# design.net
KiCad netlist of a schematic drawn in Altium Designer
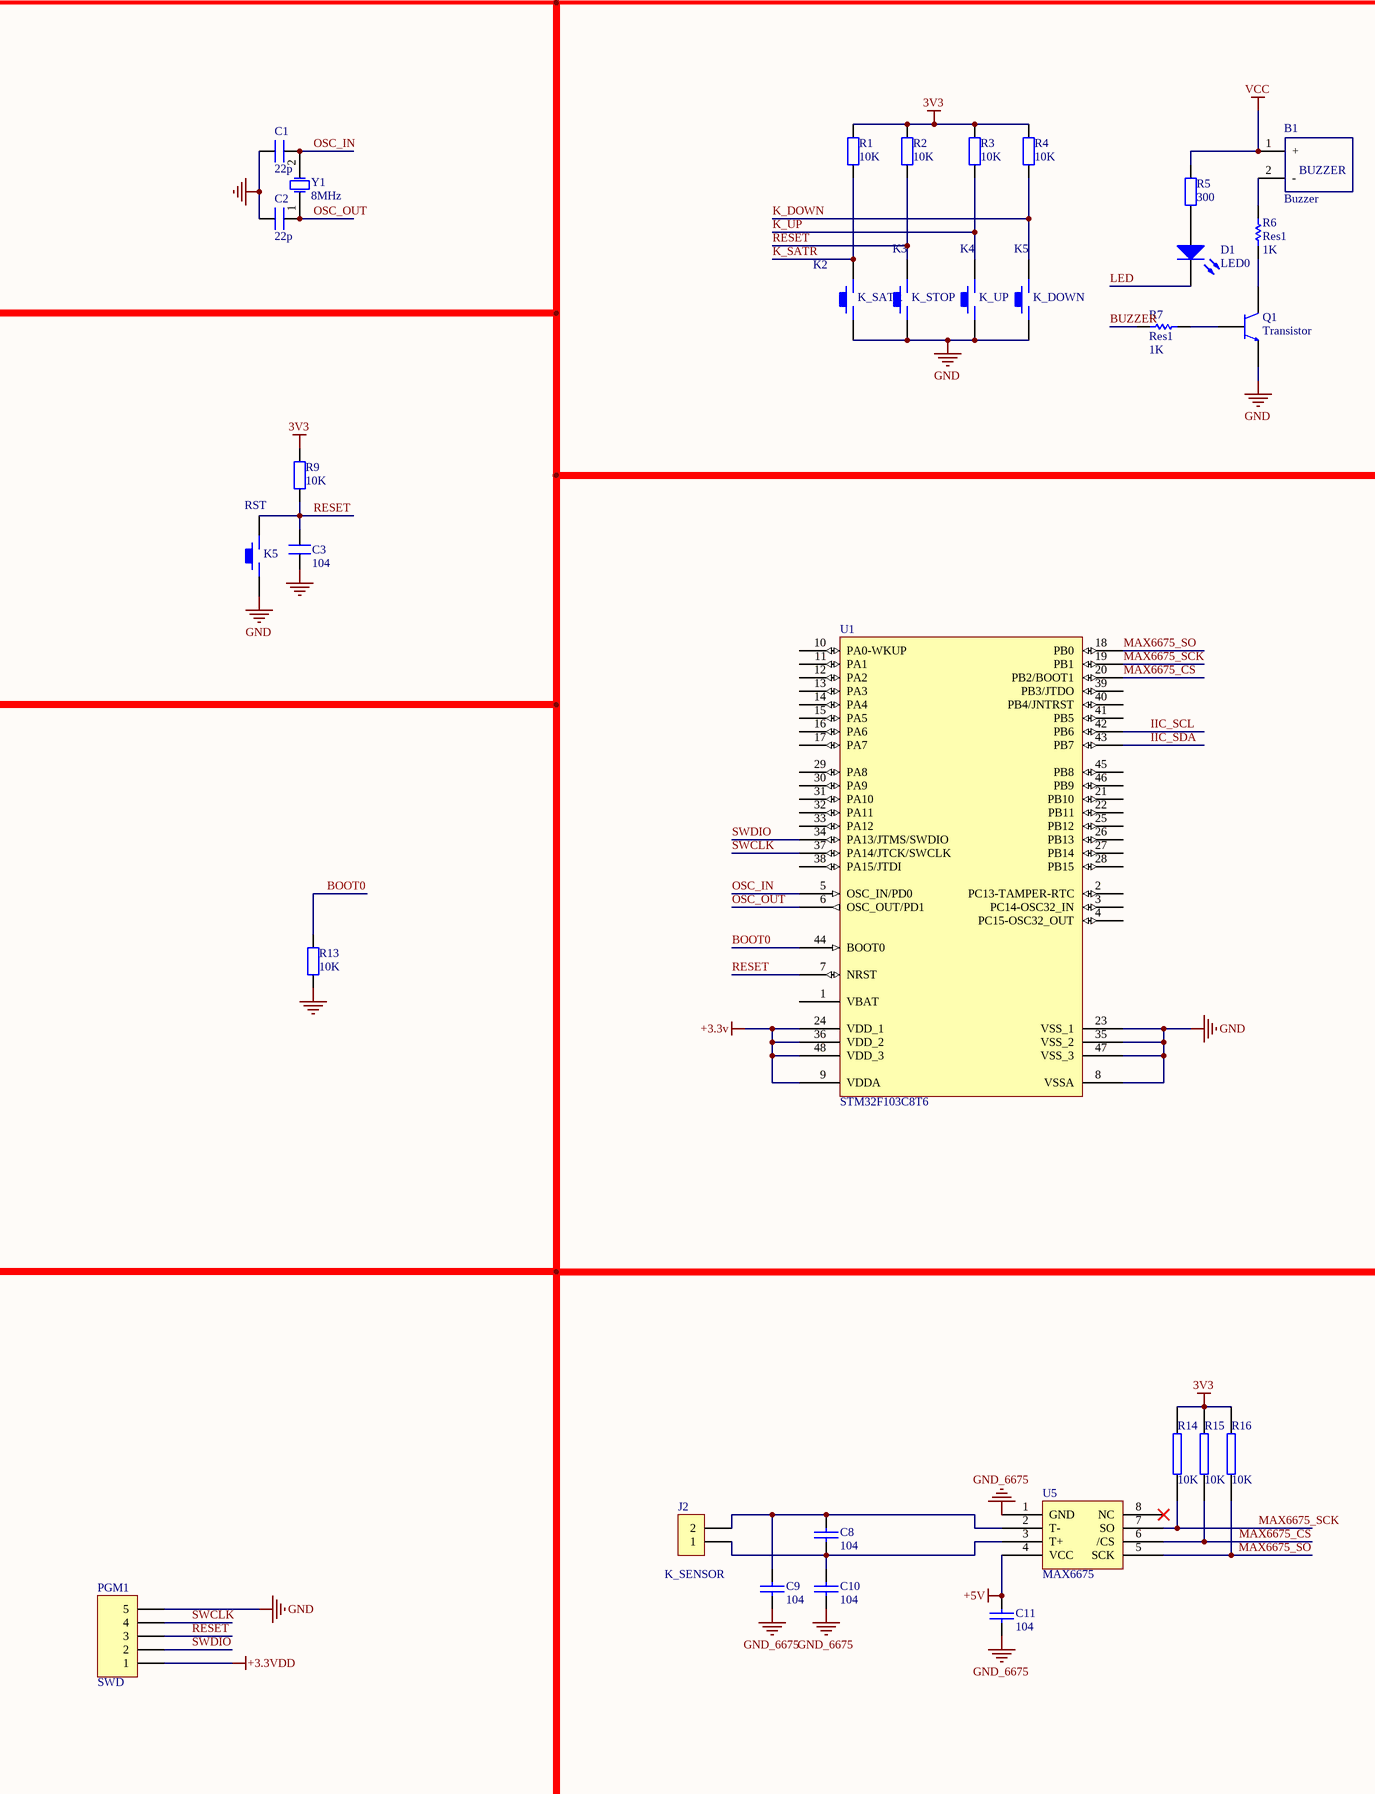
[diagram p0: 原理图.SchDoc, left]
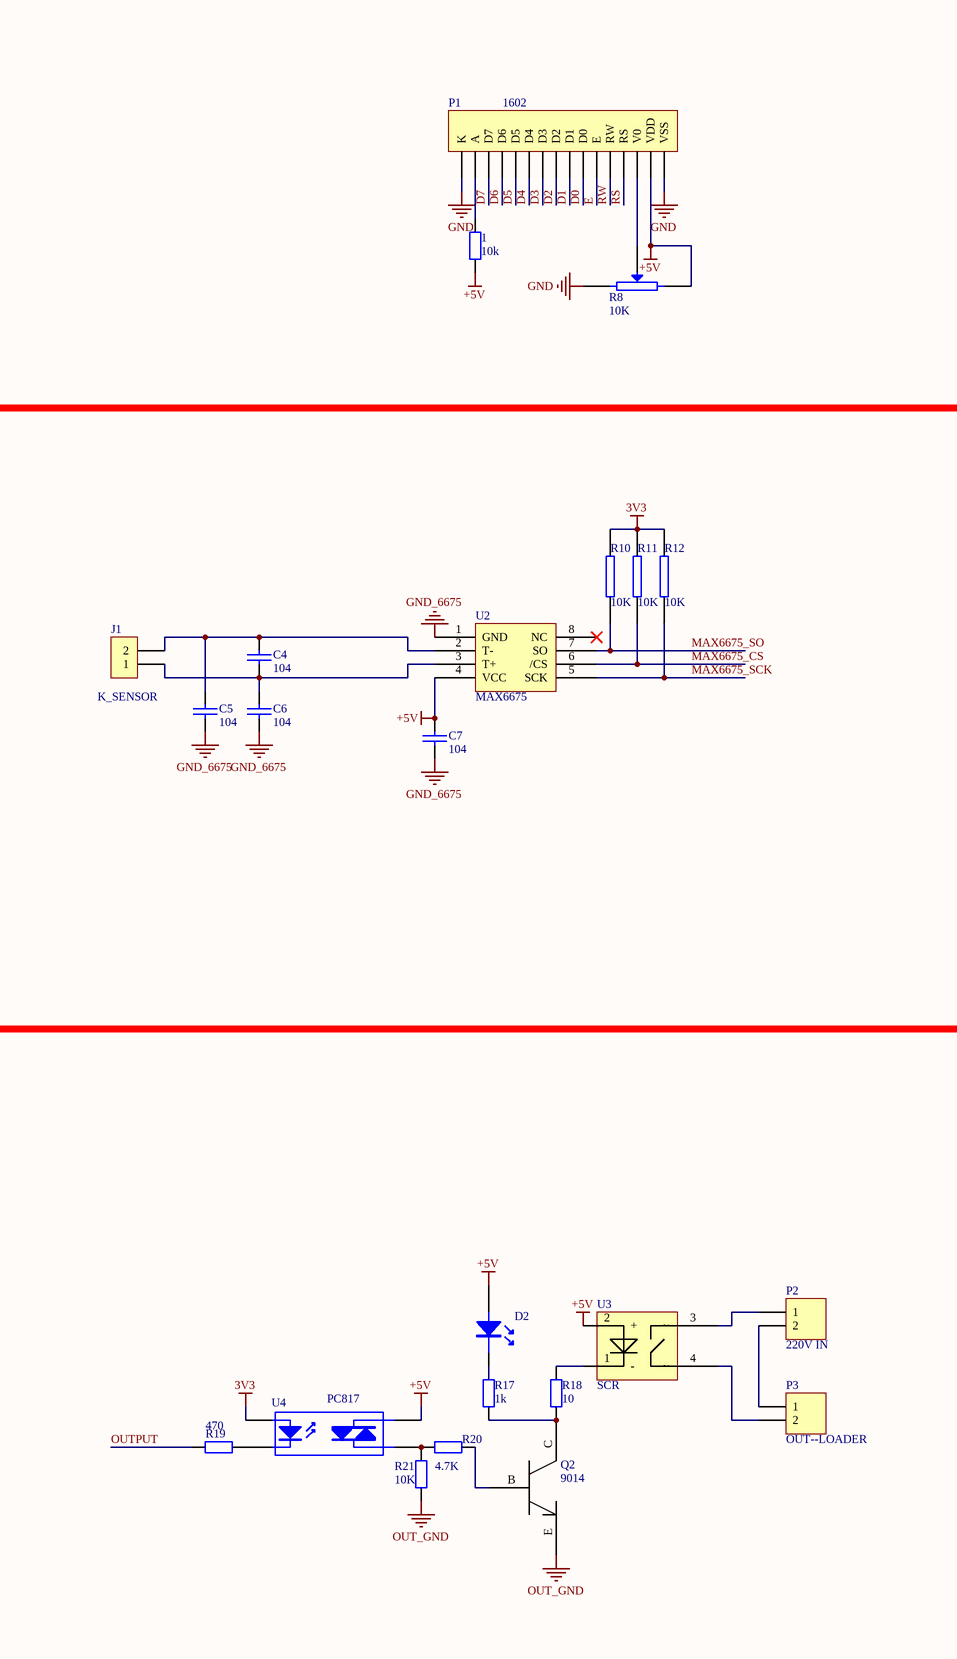
[diagram p1: 原理图.SchDoc, right]

(export (version "E")
  (design (tool "Eeschema 10.0.6"))
  (components
    (comp (ref "1")
      (value "10k")
      (footprint "AXIAL-0.4")
      (description "Resistor")
      (fields (field (name "PUBLISHER") "Altium Limited"))
      (libsource (lib "") (part "Res2_2"))
    )
    (comp (ref "B1") (value "Buzzer") (footprint "BUZZER") (libsource (lib "Second Version") (part "Buzzer")))
    (comp (ref "C1") (value "22p") (footprint "1206") (libsource (lib "MiniSTM32 V3.0封装库") (part "C")))
    (comp (ref "C2") (value "22p") (footprint "1206") (libsource (lib "MiniSTM32 V3.0封装库") (part "C")))
    (comp (ref "C3") (value "104") (footprint "1206") (libsource (lib "MiniSTM32 V3.0封装库") (part "C")))
    (comp (ref "C4")
      (value "104")
      (footprint "1206")
      (description "Capacitor")
      (libsource (lib "电容") (part "普通电容"))
    )
    (comp (ref "C5")
      (value "104")
      (footprint "1206")
      (description "Capacitor")
      (libsource (lib "电容") (part "普通电容"))
    )
    (comp (ref "C6")
      (value "104")
      (footprint "1206")
      (description "Capacitor")
      (libsource (lib "电容") (part "普通电容"))
    )
    (comp (ref "C7")
      (value "104")
      (footprint "1206")
      (description "Capacitor")
      (libsource (lib "电容") (part "普通电容"))
    )
    (comp (ref "C8")
      (value "104")
      (footprint "1206")
      (description "Capacitor")
      (libsource (lib "电容") (part "普通电容"))
    )
    (comp (ref "C9")
      (value "104")
      (footprint "1206")
      (description "Capacitor")
      (libsource (lib "电容") (part "普通电容"))
    )
    (comp (ref "C10")
      (value "104")
      (footprint "1206")
      (description "Capacitor")
      (libsource (lib "电容") (part "普通电容"))
    )
    (comp (ref "C11")
      (value "104")
      (footprint "1206")
      (description "Capacitor")
      (libsource (lib "电容") (part "普通电容"))
    )
    (comp (ref "D1")
      (value "LED0")
      (footprint "LED-0")
      (description "Typical INFRARED GaAs LED")
      (fields (field (name "PUBLISHER") "Altium Limited"))
      (libsource (lib "Miscellaneous Devices") (part "LED0"))
    )
    (comp (ref "D2") (value "~") (footprint "李建国1:LED") (libsource (lib "二极管") (part "发光二极管")))
    (comp (ref "J1")
      (value "K_SENSOR")
      (footprint "OUT_CJ")
      (description "Connector")
      (libsource (lib "Miscellaneous Devices") (part "CON2"))
    )
    (comp (ref "J2")
      (value "K_SENSOR")
      (footprint "OUT_CJ")
      (description "Connector")
      (libsource (lib "Miscellaneous Devices") (part "CON2"))
    )
    (comp (ref "K5") (value "RST") (footprint "KEY_M") (libsource (lib "底板封装库") (part "KEY_M")))
    (comp (ref "K_DOWN") (value "K5") (footprint "KEY_M") (libsource (lib "底板封装库") (part "KEY_M")))
    (comp (ref "K_SATR") (value "K2") (footprint "KEY_M") (libsource (lib "底板封装库") (part "KEY_M")))
    (comp (ref "K_STOP") (value "K3") (footprint "KEY_M") (libsource (lib "底板封装库") (part "KEY_M")))
    (comp (ref "K_UP") (value "K4") (footprint "KEY_M") (libsource (lib "底板封装库") (part "KEY_M")))
    (comp (ref "P1")
      (value "1602")
      (footprint "HDR1X16")
      (description "Header, 16-Pin")
      (fields (field (name "PUBLISHER") "Altium Limited"))
      (libsource (lib "Miscellaneous Connectors") (part "Header 16"))
    )
    (comp (ref "P2")
      (value "220V IN")
      (footprint "OUT_CJ")
      (description "Header, 2-Pin")
      (fields (field (name "PUBLISHER") "Altium Limited"))
      (libsource (lib "Miscellaneous Connectors") (part "Header 2"))
    )
    (comp (ref "P3")
      (value "OUT--LOADER")
      (footprint "OUT_CJ")
      (description "Header, 2-Pin")
      (fields (field (name "PUBLISHER") "Altium Limited"))
      (libsource (lib "Miscellaneous Connectors") (part "Header 2"))
    )
    (comp (ref "PGM1")
      (value "SWD")
      (footprint "HX2.54-5p")
      (description "Header, 5-Pin")
      (fields (field (name "PUBLISHER") "Altium Limited"))
      (libsource (lib "Miscellaneous Connectors") (part "Header 5"))
    )
    (comp (ref "Q1")
      (value "Transistor")
      (footprint "SOT23_TR")
      (libsource (lib "First Version") (part "NPN_Transistor_SOT23"))
    )
    (comp (ref "Q2") (value "9014") (footprint "9014") (libsource (lib "陈志伟2") (part "9014")))
    (comp (ref "R1")
      (value "10K")
      (footprint "1206")
      (description "Resistor")
      (fields (field (name "PUBLISHER") "Altium Limited"))
      (libsource (lib "") (part "Res2_1"))
    )
    (comp (ref "R2")
      (value "10K")
      (footprint "1206")
      (description "Resistor")
      (fields (field (name "PUBLISHER") "Altium Limited"))
      (libsource (lib "") (part "Res2_1"))
    )
    (comp (ref "R3")
      (value "10K")
      (footprint "1206")
      (description "Resistor")
      (fields (field (name "PUBLISHER") "Altium Limited"))
      (libsource (lib "") (part "Res2_1"))
    )
    (comp (ref "R4")
      (value "10K")
      (footprint "1206")
      (description "Resistor")
      (fields (field (name "PUBLISHER") "Altium Limited"))
      (libsource (lib "") (part "Res2_1"))
    )
    (comp (ref "R5")
      (value "300")
      (footprint "AXIAL-0.4")
      (description "Resistor")
      (fields (field (name "PUBLISHER") "Altium Limited"))
      (libsource (lib "") (part "Res2_2"))
    )
    (comp (ref "R6")
      (value "Res1")
      (footprint "SMD0805_RES")
      (description "Resistor")
      (fields (field (name "ALTIUM_VALUE") "1K") (field (name "PUBLISHER") "Altium Limited"))
      (libsource (lib "Miscellaneous Devices") (part "Res1"))
    )
    (comp (ref "R7")
      (value "Res1")
      (footprint "SMD0805_RES")
      (description "Resistor")
      (fields (field (name "ALTIUM_VALUE") "1K") (field (name "PUBLISHER") "Altium Limited"))
      (libsource (lib "Miscellaneous Devices") (part "Res1"))
    )
    (comp (ref "R8")
      (value "10K")
      (footprint "VR")
      (description "Potentiometer")
      (libsource (lib "电阻") (part "RESVR"))
    )
    (comp (ref "R9")
      (value "10K")
      (footprint "1206")
      (description "Resistor")
      (fields (field (name "PUBLISHER") "Altium Limited"))
      (libsource (lib "Miscellaneous Devices") (part "Res2"))
    )
    (comp (ref "R10") (value "10K") (footprint "1206") (libsource (lib "*") (part "RES2")))
    (comp (ref "R11") (value "10K") (footprint "1206") (libsource (lib "*") (part "RES2")))
    (comp (ref "R12") (value "10K") (footprint "1206") (libsource (lib "*") (part "RES2")))
    (comp (ref "R13")
      (value "10K")
      (footprint "1206")
      (description "Resistor")
      (fields (field (name "PUBLISHER") "Altium Limited"))
      (libsource (lib "Miscellaneous Devices") (part "Res2"))
    )
    (comp (ref "R14") (value "10K") (footprint "1206") (libsource (lib "*") (part "RES2")))
    (comp (ref "R15") (value "10K") (footprint "1206") (libsource (lib "*") (part "RES2")))
    (comp (ref "R16") (value "10K") (footprint "1206") (libsource (lib "*") (part "RES2")))
    (comp (ref "R17")
      (value "1k")
      (footprint "1206")
      (description "Resistor")
      (fields (field (name "PUBLISHER") "Altium Limited"))
      (libsource (lib "") (part "Res2_1"))
    )
    (comp (ref "R18")
      (value "10")
      (footprint "1206")
      (description "Resistor")
      (fields (field (name "PUBLISHER") "Altium Limited"))
      (libsource (lib "") (part "Res2_1"))
    )
    (comp (ref "R19")
      (value "470")
      (footprint "1206")
      (description "Resistor")
      (fields (field (name "PUBLISHER") "Altium Limited"))
      (libsource (lib "Miscellaneous Devices") (part "Res2"))
    )
    (comp (ref "R20")
      (value "4.7K")
      (footprint "1206")
      (description "Resistor")
      (fields (field (name "PUBLISHER") "Altium Limited"))
      (libsource (lib "Miscellaneous Devices") (part "Res2"))
    )
    (comp (ref "R21")
      (value "10K")
      (footprint "1206")
      (description "Resistor")
      (fields (field (name "PUBLISHER") "Altium Limited"))
      (libsource (lib "") (part "Res2_1"))
    )
    (comp (ref "U1")
      (value "STM32F103C8T6")
      (footprint "LQFP48_N")
      (description "STM32 ARM-based 32-bit MCU with 64 Kbytes Flash, 48-pin LQFP, Industrial Temperature")
      (fields (field (name "PUBLISHER") "Altium Limited"))
      (libsource (lib "ST Microcontroller 32-Bit STM32") (part "STM32F103C8T6"))
    )
    (comp (ref "U2") (value "MAX6675") (footprint "SO-8") (libsource (lib "温控库") (part "MAX6675")))
    (comp (ref "U3") (value "SCR") (footprint "SCR") (libsource (lib "*") (part "SCR")))
    (comp (ref "U4")
      (value "PC817")
      (footprint "pc817")
      (libsource (lib "Miscellaneous Devices") (part "OPTOTRIAC"))
    )
    (comp (ref "U5") (value "MAX6675") (footprint "SO-8") (libsource (lib "温控库") (part "MAX6675")))
    (comp (ref "Y1")
      (value "8MHz")
      (footprint "XTAL_US")
      (description "Crystal Oscillator")
      (fields (field (name "PUBLISHER") "Altium Limited"))
      (libsource (lib "MiniSTM32 V3.0封装库") (part "XTAL"))
    )
  )
  (nets
    (net (code "1") (name "+3.3VDD") (class "Default")
      (node (ref "PGM1") (pin "1") (pinfunction "1_1") (pintype "passive"))
    )
    (net (code "2") (name "+3.3v") (class "Default")
      (node (ref "U1") (pin "24") (pinfunction "VDD_1_24") (pintype "power_in"))
      (node (ref "U1") (pin "36") (pinfunction "VDD_2_36") (pintype "power_in"))
      (node (ref "U1") (pin "48") (pinfunction "VDD_3_48") (pintype "power_in"))
      (node (ref "U1") (pin "9") (pinfunction "VDDA_9") (pintype "power_in"))
    )
    (net (code "3") (name "+5V") (class "Default")
      (node (ref "1") (pin "1") (pinfunction "1_1") (pintype "passive"))
      (node (ref "C11") (pin "1") (pinfunction "1_1") (pintype "passive"))
      (node (ref "C7") (pin "1") (pinfunction "1_1") (pintype "passive"))
      (node (ref "D2") (pin "A") (pinfunction "1_A") (pintype "passive"))
      (node (ref "P1") (pin "2") (pinfunction "VDD_2") (pintype "passive"))
      (node (ref "R8") (pin "2") (pinfunction "2_2") (pintype "passive"))
      (node (ref "U2") (pin "4") (pinfunction "VCC_4") (pintype "passive"))
      (node (ref "U3") (pin "2") (pinfunction "+_2") (pintype "passive"))
      (node (ref "U4") (pin "3") (pinfunction "A/K_3") (pintype "passive"))
      (node (ref "U5") (pin "4") (pinfunction "VCC_4") (pintype "passive"))
    )
    (net (code "4") (name "/BOOT0") (class "Default")
      (node (ref "R13") (pin "1") (pinfunction "1_1") (pintype "passive"))
      (node (ref "U1") (pin "44") (pinfunction "BOOT0_44") (pintype "input"))
    )
    (net (code "5") (name "/BUZZER") (class "Default")
      (node (ref "R7") (pin "1") (pinfunction "1_1") (pintype "passive"))
    )
    (net (code "6") (name "/D0") (class "Default")
      (node (ref "P1") (pin "7") (pinfunction "D0_7") (pintype "passive"))
    )
    (net (code "7") (name "/D1") (class "Default")
      (node (ref "P1") (pin "8") (pinfunction "D1_8") (pintype "passive"))
    )
    (net (code "8") (name "/D2") (class "Default")
      (node (ref "P1") (pin "9") (pinfunction "D2_9") (pintype "passive"))
    )
    (net (code "9") (name "/D3") (class "Default")
      (node (ref "P1") (pin "10") (pinfunction "D3_10") (pintype "passive"))
    )
    (net (code "10") (name "/D4") (class "Default")
      (node (ref "P1") (pin "11") (pinfunction "D4_11") (pintype "passive"))
    )
    (net (code "11") (name "/D5") (class "Default")
      (node (ref "P1") (pin "12") (pinfunction "D5_12") (pintype "passive"))
    )
    (net (code "12") (name "/D6") (class "Default")
      (node (ref "P1") (pin "13") (pinfunction "D6_13") (pintype "passive"))
    )
    (net (code "13") (name "/D7") (class "Default")
      (node (ref "P1") (pin "14") (pinfunction "D7_14") (pintype "passive"))
    )
    (net (code "14") (name "/E") (class "Default")
      (node (ref "P1") (pin "6") (pinfunction "E_6") (pintype "passive"))
    )
    (net (code "15") (name "/IIC_SCL") (class "Default")
      (node (ref "U1") (pin "42") (pinfunction "PB6_42") (pintype "bidirectional"))
    )
    (net (code "16") (name "/IIC_SDA") (class "Default")
      (node (ref "U1") (pin "43") (pinfunction "PB7_43") (pintype "bidirectional"))
    )
    (net (code "17") (name "/K_DOWN") (class "Default")
      (node (ref "K_DOWN") (pin "2") (pinfunction "2_2") (pintype "passive"))
      (node (ref "R4") (pin "1") (pinfunction "1_1") (pintype "passive"))
    )
    (net (code "18") (name "/K_SATR") (class "Default")
      (node (ref "K_SATR") (pin "2") (pinfunction "2_2") (pintype "passive"))
      (node (ref "R1") (pin "1") (pinfunction "1_1") (pintype "passive"))
    )
    (net (code "19") (name "/K_UP") (class "Default")
      (node (ref "K_UP") (pin "2") (pinfunction "2_2") (pintype "passive"))
      (node (ref "R3") (pin "1") (pinfunction "1_1") (pintype "passive"))
    )
    (net (code "20") (name "/LED") (class "Default")
      (node (ref "D1") (pin "2") (pinfunction "K_2") (pintype "passive"))
    )
    (net (code "21") (name "/MAX6675_CS") (class "Default")
      (node (ref "R11") (pin "1") (pinfunction "1_1") (pintype "passive"))
      (node (ref "R15") (pin "1") (pinfunction "1_1") (pintype "passive"))
      (node (ref "U1") (pin "20") (pinfunction "PB2/BOOT1_20") (pintype "bidirectional"))
      (node (ref "U2") (pin "6") (pinfunction "/CS_6") (pintype "passive"))
      (node (ref "U5") (pin "6") (pinfunction "/CS_6") (pintype "passive"))
    )
    (net (code "22") (name "/MAX6675_SCK") (class "Default")
      (node (ref "R12") (pin "1") (pinfunction "1_1") (pintype "passive"))
      (node (ref "R14") (pin "1") (pinfunction "1_1") (pintype "passive"))
      (node (ref "U1") (pin "19") (pinfunction "PB1_19") (pintype "bidirectional"))
      (node (ref "U2") (pin "5") (pinfunction "SCK_5") (pintype "passive"))
      (node (ref "U5") (pin "7") (pinfunction "SO_7") (pintype "passive"))
    )
    (net (code "23") (name "/MAX6675_SO") (class "Default")
      (node (ref "R10") (pin "1") (pinfunction "1_1") (pintype "passive"))
      (node (ref "R16") (pin "1") (pinfunction "1_1") (pintype "passive"))
      (node (ref "U1") (pin "18") (pinfunction "PB0_18") (pintype "bidirectional"))
      (node (ref "U2") (pin "7") (pinfunction "SO_7") (pintype "passive"))
      (node (ref "U5") (pin "5") (pinfunction "SCK_5") (pintype "passive"))
    )
    (net (code "24") (name "/OSC_IN") (class "Default")
      (node (ref "C1") (pin "1") (pintype "passive"))
      (node (ref "U1") (pin "5") (pinfunction "OSC_IN/PD0_5") (pintype "input"))
      (node (ref "Y1") (pin "2") (pinfunction "OSC2_2") (pintype "passive"))
    )
    (net (code "25") (name "/OSC_OUT") (class "Default")
      (node (ref "C2") (pin "2") (pintype "passive"))
      (node (ref "U1") (pin "6") (pinfunction "OSC_OUT/PD1_6") (pintype "output"))
      (node (ref "Y1") (pin "1") (pinfunction "OSC1_1") (pintype "passive"))
    )
    (net (code "26") (name "/OUTPUT") (class "Default")
      (node (ref "R19") (pin "2") (pinfunction "2_2") (pintype "passive"))
    )
    (net (code "27") (name "/RESET") (class "Default")
      (node (ref "C3") (pin "1") (pintype "passive"))
      (node (ref "K5") (pin "2") (pinfunction "2_2") (pintype "passive"))
      (node (ref "K_STOP") (pin "2") (pinfunction "2_2") (pintype "passive"))
      (node (ref "PGM1") (pin "3") (pinfunction "3_3") (pintype "passive"))
      (node (ref "R2") (pin "1") (pinfunction "1_1") (pintype "passive"))
      (node (ref "R9") (pin "2") (pinfunction "2_2") (pintype "passive"))
      (node (ref "U1") (pin "7") (pinfunction "NRST_7") (pintype "bidirectional"))
    )
    (net (code "28") (name "/RS") (class "Default")
      (node (ref "P1") (pin "4") (pinfunction "RS_4") (pintype "passive"))
    )
    (net (code "29") (name "/RW") (class "Default")
      (node (ref "P1") (pin "5") (pinfunction "RW_5") (pintype "passive"))
    )
    (net (code "30") (name "/SWCLK") (class "Default")
      (node (ref "PGM1") (pin "4") (pinfunction "4_4") (pintype "passive"))
      (node (ref "U1") (pin "37") (pinfunction "PA14/JTCK/SWCLK_37") (pintype "bidirectional"))
    )
    (net (code "31") (name "/SWDIO") (class "Default")
      (node (ref "PGM1") (pin "2") (pinfunction "2_2") (pintype "passive"))
      (node (ref "U1") (pin "34") (pinfunction "PA13/JTMS/SWDIO_34") (pintype "bidirectional"))
    )
    (net (code "32") (name "3V3") (class "Default")
      (node (ref "R1") (pin "2") (pinfunction "2_2") (pintype "passive"))
      (node (ref "R10") (pin "2") (pinfunction "2_2") (pintype "passive"))
      (node (ref "R11") (pin "2") (pinfunction "2_2") (pintype "passive"))
      (node (ref "R12") (pin "2") (pinfunction "2_2") (pintype "passive"))
      (node (ref "R14") (pin "2") (pinfunction "2_2") (pintype "passive"))
      (node (ref "R15") (pin "2") (pinfunction "2_2") (pintype "passive"))
      (node (ref "R16") (pin "2") (pinfunction "2_2") (pintype "passive"))
      (node (ref "R2") (pin "2") (pinfunction "2_2") (pintype "passive"))
      (node (ref "R3") (pin "2") (pinfunction "2_2") (pintype "passive"))
      (node (ref "R4") (pin "2") (pinfunction "2_2") (pintype "passive"))
      (node (ref "R9") (pin "1") (pinfunction "1_1") (pintype "passive"))
      (node (ref "U4") (pin "1") (pinfunction "A_1") (pintype "passive"))
    )
    (net (code "33") (name "GND") (class "Default")
      (node (ref "C1") (pin "2") (pintype "passive"))
      (node (ref "C2") (pin "1") (pintype "passive"))
      (node (ref "C3") (pin "2") (pintype "passive"))
      (node (ref "K5") (pin "1") (pinfunction "1_1") (pintype "passive"))
      (node (ref "K_DOWN") (pin "1") (pinfunction "1_1") (pintype "passive"))
      (node (ref "K_SATR") (pin "1") (pinfunction "1_1") (pintype "passive"))
      (node (ref "K_STOP") (pin "1") (pinfunction "1_1") (pintype "passive"))
      (node (ref "K_UP") (pin "1") (pinfunction "1_1") (pintype "passive"))
      (node (ref "P1") (pin "1") (pinfunction "VSS_1") (pintype "passive"))
      (node (ref "P1") (pin "16") (pinfunction "K_16") (pintype "passive"))
      (node (ref "PGM1") (pin "5") (pinfunction "5_5") (pintype "passive"))
      (node (ref "Q1") (pin "2") (pinfunction "2_2") (pintype "passive"))
      (node (ref "R13") (pin "2") (pinfunction "2_2") (pintype "passive"))
      (node (ref "R8") (pin "1") (pinfunction "1_1") (pintype "passive"))
      (node (ref "U1") (pin "23") (pinfunction "VSS_1_23") (pintype "power_in"))
      (node (ref "U1") (pin "35") (pinfunction "VSS_2_35") (pintype "power_in"))
      (node (ref "U1") (pin "47") (pinfunction "VSS_3_47") (pintype "power_in"))
      (node (ref "U1") (pin "8") (pinfunction "VSSA_8") (pintype "power_in"))
    )
    (net (code "34") (name "GND_6675") (class "Default")
      (node (ref "C10") (pin "2") (pinfunction "2_2") (pintype "passive"))
      (node (ref "C11") (pin "2") (pinfunction "2_2") (pintype "passive"))
      (node (ref "C5") (pin "2") (pinfunction "2_2") (pintype "passive"))
      (node (ref "C6") (pin "2") (pinfunction "2_2") (pintype "passive"))
      (node (ref "C7") (pin "2") (pinfunction "2_2") (pintype "passive"))
      (node (ref "C9") (pin "2") (pinfunction "2_2") (pintype "passive"))
      (node (ref "U2") (pin "1") (pinfunction "GND_1") (pintype "passive"))
      (node (ref "U5") (pin "1") (pinfunction "GND_1") (pintype "passive"))
    )
    (net (code "35") (name "Net-(B1--)") (class "Default")
      (node (ref "B1") (pin "2") (pinfunction "-_2") (pintype "passive"))
      (node (ref "R6") (pin "2") (pinfunction "2_2") (pintype "passive"))
    )
    (net (code "36") (name "Net-(D1-A)") (class "Default")
      (node (ref "D1") (pin "1") (pinfunction "A_1") (pintype "passive"))
      (node (ref "R5") (pin "1") (pinfunction "1_1") (pintype "passive"))
    )
    (net (code "37") (name "Net-(D2-2)") (class "Default")
      (node (ref "D2") (pin "K") (pinfunction "2_K") (pintype "passive"))
      (node (ref "R17") (pin "2") (pinfunction "2_2") (pintype "passive"))
    )
    (net (code "38") (name "Net-(P1-A)") (class "Default")
      (node (ref "1") (pin "2") (pinfunction "2_2") (pintype "passive"))
      (node (ref "P1") (pin "15") (pinfunction "A_15") (pintype "passive"))
    )
    (net (code "39") (name "Net-(P1-V0)") (class "Default")
      (node (ref "P1") (pin "3") (pinfunction "V0_3") (pintype "passive"))
      (node (ref "R8") (pin "3") (pinfunction "W_3") (pintype "passive"))
    )
    (net (code "40") (name "Net-(P2-Pad1)") (class "Default")
      (node (ref "P2") (pin "1") (pinfunction "1_1") (pintype "passive"))
      (node (ref "U3") (pin "3") (pinfunction "~_3") (pintype "passive"))
    )
    (net (code "41") (name "Net-(P2-Pad2)") (class "Default")
      (node (ref "P2") (pin "2") (pinfunction "2_2") (pintype "passive"))
      (node (ref "P3") (pin "1") (pinfunction "1_1") (pintype "passive"))
    )
    (net (code "42") (name "Net-(P3-Pad2)") (class "Default")
      (node (ref "P3") (pin "2") (pinfunction "2_2") (pintype "passive"))
      (node (ref "U3") (pin "4") (pinfunction "~_4") (pintype "passive"))
    )
    (net (code "43") (name "Net-(Q1-Pad1)") (class "Default")
      (node (ref "Q1") (pin "1") (pinfunction "1_1") (pintype "passive"))
      (node (ref "R7") (pin "2") (pinfunction "2_2") (pintype "passive"))
    )
    (net (code "44") (name "Net-(Q1-Pad3)") (class "Default")
      (node (ref "Q1") (pin "3") (pinfunction "3_3") (pintype "passive"))
      (node (ref "R6") (pin "1") (pinfunction "1_1") (pintype "passive"))
    )
    (net (code "45") (name "Net-(Q2-PadB)") (class "Default")
      (node (ref "Q2") (pin "B") (pinfunction "B_B") (pintype "passive"))
      (node (ref "R20") (pin "1") (pinfunction "1_1") (pintype "passive"))
    )
    (net (code "46") (name "Net-(Q2-PadC)") (class "Default")
      (node (ref "Q2") (pin "C") (pinfunction "C_C") (pintype "passive"))
      (node (ref "R17") (pin "1") (pinfunction "1_1") (pintype "passive"))
      (node (ref "R18") (pin "1") (pinfunction "1_1") (pintype "passive"))
    )
    (net (code "47") (name "Net-(R20-Pad2)") (class "Default")
      (node (ref "R20") (pin "2") (pinfunction "2_2") (pintype "passive"))
      (node (ref "R21") (pin "2") (pinfunction "2_2") (pintype "passive"))
      (node (ref "U4") (pin "4") (pinfunction "A/K_4") (pintype "passive"))
    )
    (net (code "48") (name "Net-(U2-T+)") (class "Default")
      (node (ref "C4") (pin "2") (pinfunction "2_2") (pintype "passive"))
      (node (ref "C6") (pin "1") (pinfunction "1_1") (pintype "passive"))
      (node (ref "J1") (pin "1") (pinfunction "1_1") (pintype "passive"))
      (node (ref "U2") (pin "3") (pinfunction "T+_3") (pintype "passive"))
    )
    (net (code "49") (name "Net-(U2-T-)") (class "Default")
      (node (ref "C4") (pin "1") (pinfunction "1_1") (pintype "passive"))
      (node (ref "C5") (pin "1") (pinfunction "1_1") (pintype "passive"))
      (node (ref "J1") (pin "2") (pinfunction "2_2") (pintype "passive"))
      (node (ref "U2") (pin "2") (pinfunction "T-_2") (pintype "passive"))
    )
    (net (code "50") (name "Net-(U3--)") (class "Default")
      (node (ref "R18") (pin "2") (pinfunction "2_2") (pintype "passive"))
      (node (ref "U3") (pin "1") (pinfunction "-_1") (pintype "passive"))
    )
    (net (code "51") (name "Net-(U4-K)") (class "Default")
      (node (ref "R19") (pin "1") (pinfunction "1_1") (pintype "passive"))
      (node (ref "U4") (pin "2") (pinfunction "K_2") (pintype "passive"))
    )
    (net (code "52") (name "Net-(U5-T+)") (class "Default")
      (node (ref "C10") (pin "1") (pinfunction "1_1") (pintype "passive"))
      (node (ref "C8") (pin "2") (pinfunction "2_2") (pintype "passive"))
      (node (ref "J2") (pin "1") (pinfunction "1_1") (pintype "passive"))
      (node (ref "U5") (pin "3") (pinfunction "T+_3") (pintype "passive"))
    )
    (net (code "53") (name "Net-(U5-T-)") (class "Default")
      (node (ref "C8") (pin "1") (pinfunction "1_1") (pintype "passive"))
      (node (ref "C9") (pin "1") (pinfunction "1_1") (pintype "passive"))
      (node (ref "J2") (pin "2") (pinfunction "2_2") (pintype "passive"))
      (node (ref "U5") (pin "2") (pinfunction "T-_2") (pintype "passive"))
    )
    (net (code "54") (name "OUT_GND") (class "Default")
      (node (ref "Q2") (pin "E") (pinfunction "E_E") (pintype "passive"))
      (node (ref "R21") (pin "1") (pinfunction "1_1") (pintype "passive"))
    )
    (net (code "55") (name "VCC") (class "Default")
      (node (ref "B1") (pin "1") (pinfunction "+_1") (pintype "passive"))
      (node (ref "R5") (pin "2") (pinfunction "2_2") (pintype "passive"))
    )
    (net (code "56") (name "unconnected-(U1-PA0-WKUP-Pad10)") (class "Default")
      (node (ref "U1") (pin "10") (pinfunction "PA0-WKUP_10") (pintype "bidirectional"))
    )
    (net (code "57") (name "unconnected-(U1-PA1-Pad11)") (class "Default")
      (node (ref "U1") (pin "11") (pinfunction "PA1_11") (pintype "bidirectional"))
    )
    (net (code "58") (name "unconnected-(U1-PA2-Pad12)") (class "Default")
      (node (ref "U1") (pin "12") (pinfunction "PA2_12") (pintype "bidirectional"))
    )
    (net (code "59") (name "unconnected-(U1-PA3-Pad13)") (class "Default")
      (node (ref "U1") (pin "13") (pinfunction "PA3_13") (pintype "bidirectional"))
    )
    (net (code "60") (name "unconnected-(U1-PA4-Pad14)") (class "Default")
      (node (ref "U1") (pin "14") (pinfunction "PA4_14") (pintype "bidirectional"))
    )
    (net (code "61") (name "unconnected-(U1-PA5-Pad15)") (class "Default")
      (node (ref "U1") (pin "15") (pinfunction "PA5_15") (pintype "bidirectional"))
    )
    (net (code "62") (name "unconnected-(U1-PA6-Pad16)") (class "Default")
      (node (ref "U1") (pin "16") (pinfunction "PA6_16") (pintype "bidirectional"))
    )
    (net (code "63") (name "unconnected-(U1-PA7-Pad17)") (class "Default")
      (node (ref "U1") (pin "17") (pinfunction "PA7_17") (pintype "bidirectional"))
    )
    (net (code "64") (name "unconnected-(U1-PA8-Pad29)") (class "Default")
      (node (ref "U1") (pin "29") (pinfunction "PA8_29") (pintype "bidirectional"))
    )
    (net (code "65") (name "unconnected-(U1-PA9-Pad30)") (class "Default")
      (node (ref "U1") (pin "30") (pinfunction "PA9_30") (pintype "bidirectional"))
    )
    (net (code "66") (name "unconnected-(U1-PA10-Pad31)") (class "Default")
      (node (ref "U1") (pin "31") (pinfunction "PA10_31") (pintype "bidirectional"))
    )
    (net (code "67") (name "unconnected-(U1-PA11-Pad32)") (class "Default")
      (node (ref "U1") (pin "32") (pinfunction "PA11_32") (pintype "bidirectional"))
    )
    (net (code "68") (name "unconnected-(U1-PA12-Pad33)") (class "Default")
      (node (ref "U1") (pin "33") (pinfunction "PA12_33") (pintype "bidirectional"))
    )
    (net (code "69") (name "unconnected-(U1-PA15{slash}JTDI-Pad38)") (class "Default")
      (node (ref "U1") (pin "38") (pinfunction "PA15/JTDI_38") (pintype "bidirectional"))
    )
    (net (code "70") (name "unconnected-(U1-PB3{slash}JTDO-Pad39)") (class "Default")
      (node (ref "U1") (pin "39") (pinfunction "PB3/JTDO_39") (pintype "bidirectional"))
    )
    (net (code "71") (name "unconnected-(U1-PB4{slash}JNTRST-Pad40)") (class "Default")
      (node (ref "U1") (pin "40") (pinfunction "PB4/JNTRST_40") (pintype "bidirectional"))
    )
    (net (code "72") (name "unconnected-(U1-PB5-Pad41)") (class "Default")
      (node (ref "U1") (pin "41") (pinfunction "PB5_41") (pintype "bidirectional"))
    )
    (net (code "73") (name "unconnected-(U1-PB8-Pad45)") (class "Default")
      (node (ref "U1") (pin "45") (pinfunction "PB8_45") (pintype "bidirectional"))
    )
    (net (code "74") (name "unconnected-(U1-PB9-Pad46)") (class "Default")
      (node (ref "U1") (pin "46") (pinfunction "PB9_46") (pintype "bidirectional"))
    )
    (net (code "75") (name "unconnected-(U1-PB10-Pad21)") (class "Default")
      (node (ref "U1") (pin "21") (pinfunction "PB10_21") (pintype "bidirectional"))
    )
    (net (code "76") (name "unconnected-(U1-PB11-Pad22)") (class "Default")
      (node (ref "U1") (pin "22") (pinfunction "PB11_22") (pintype "bidirectional"))
    )
    (net (code "77") (name "unconnected-(U1-PB12-Pad25)") (class "Default")
      (node (ref "U1") (pin "25") (pinfunction "PB12_25") (pintype "bidirectional"))
    )
    (net (code "78") (name "unconnected-(U1-PB13-Pad26)") (class "Default")
      (node (ref "U1") (pin "26") (pinfunction "PB13_26") (pintype "bidirectional"))
    )
    (net (code "79") (name "unconnected-(U1-PB14-Pad27)") (class "Default")
      (node (ref "U1") (pin "27") (pinfunction "PB14_27") (pintype "bidirectional"))
    )
    (net (code "80") (name "unconnected-(U1-PB15-Pad28)") (class "Default")
      (node (ref "U1") (pin "28") (pinfunction "PB15_28") (pintype "bidirectional"))
    )
    (net (code "81") (name "unconnected-(U1-PC13-TAMPER-RTC-Pad2)") (class "Default")
      (node (ref "U1") (pin "2") (pinfunction "PC13-TAMPER-RTC_2") (pintype "bidirectional"))
    )
    (net (code "82") (name "unconnected-(U1-PC14-OSC32_IN-Pad3)") (class "Default")
      (node (ref "U1") (pin "3") (pinfunction "PC14-OSC32_IN_3") (pintype "bidirectional"))
    )
    (net (code "83") (name "unconnected-(U1-PC15-OSC32_OUT-Pad4)") (class "Default")
      (node (ref "U1") (pin "4") (pinfunction "PC15-OSC32_OUT_4") (pintype "bidirectional"))
    )
    (net (code "84") (name "unconnected-(U1-VBAT-Pad1)") (class "Default")
      (node (ref "U1") (pin "1") (pinfunction "VBAT_1") (pintype "power_in"))
    )
    (net (code "85") (name "unconnected-(U2-NC-Pad8)") (class "Default")
      (node (ref "U2") (pin "8") (pinfunction "NC_8") (pintype "passive+no_connect"))
    )
    (net (code "86") (name "unconnected-(U5-NC-Pad8)") (class "Default")
      (node (ref "U5") (pin "8") (pinfunction "NC_8") (pintype "passive+no_connect"))
    )
  )
)
